# AMP.net
KiCad netlist of a schematic drawn in Altium Designer
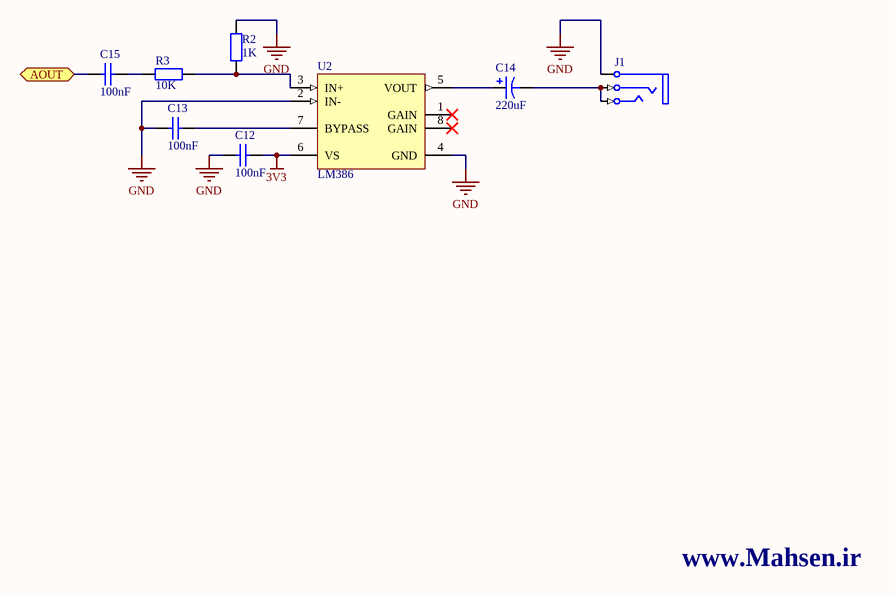
[diagram p0: AMP.SchDoc]

(export (version "E")
  (design (tool "Eeschema 10.0.6"))
  (components
    (comp (ref "C12")
      (value "100nF")
      (footprint "0805")
      (description "Capacitor")
      (fields (field (name "PUBLISHER") "Altium Limited"))
      (libsource (lib "Miscellaneous Devices") (part "Cap"))
    )
    (comp (ref "C13")
      (value "100nF")
      (footprint "0805")
      (description "Capacitor")
      (fields (field (name "PUBLISHER") "Altium Limited"))
      (libsource (lib "Miscellaneous Devices") (part "Cap"))
    )
    (comp (ref "C14")
      (value "220uF")
      (footprint "C0805")
      (description "Polarized Capacitor (Surface Mount)")
      (fields (field (name "PUBLISHER") "Altium Limited"))
      (libsource (lib "Miscellaneous Devices") (part "Cap Pol3"))
    )
    (comp (ref "C15")
      (value "100nF")
      (footprint "0805")
      (description "Capacitor")
      (fields (field (name "PUBLISHER") "Altium Limited"))
      (libsource (lib "Miscellaneous Devices") (part "Cap"))
    )
    (comp (ref "J1")
      (value "Phonejack3")
      (footprint "JACK/6-V3")
      (description "Jack Socket, 1/4\" [6.5mm], Thru-Hole, Vertical, 3-Conductor Open Circuit (Non-Normalling)")
      (fields (field (name "PUBLISHER") "Altium Limited"))
      (libsource (lib "Miscellaneous Connectors") (part "Phonejack3"))
    )
    (comp (ref "R2")
      (value "1K")
      (footprint "0805")
      (description "Resistor")
      (fields (field (name "PUBLISHER") "Altium Limited"))
      (libsource (lib "Miscellaneous Devices") (part "Res2"))
    )
    (comp (ref "R3")
      (value "10K")
      (footprint "0805")
      (description "Resistor")
      (fields (field (name "PUBLISHER") "Altium Limited"))
      (libsource (lib "") (part "Res2_1"))
    )
    (comp (ref "U2")
      (value "LM386")
      (footprint "M08A_L")
      (description "Low Voltage Audio Power Amplifier, 8-pin Narrow SOIC")
      (fields
        (field (name "PARTNUMBER") "LM386MX-1")
        (field (name "MANUFACTURER") "National Semiconductor")
        (field (name "PUBLISHER") "Altium Limited")
      )
      (libsource (lib "NSC Audio") (part "LM386MX-1"))
    )
  )
  (nets
    (net (code "1") (name "/AOUT") (class "Default")
      (node (ref "C15") (pin "2") (pinfunction "2_2") (pintype "passive"))
    )
    (net (code "2") (name "3V3") (class "Default")
      (node (ref "C12") (pin "1") (pinfunction "1_1") (pintype "passive"))
      (node (ref "U2") (pin "6") (pinfunction "VS_6") (pintype "power_in"))
    )
    (net (code "3") (name "GND") (class "Default")
      (node (ref "C12") (pin "2") (pinfunction "2_2") (pintype "passive"))
      (node (ref "C13") (pin "2") (pinfunction "2_2") (pintype "passive"))
      (node (ref "J1") (pin "5") (pinfunction "S_5") (pintype "power_in"))
      (node (ref "R2") (pin "2") (pinfunction "2_2") (pintype "passive"))
      (node (ref "U2") (pin "2") (pinfunction "IN-_2") (pintype "input"))
      (node (ref "U2") (pin "4") (pinfunction "GND_4") (pintype "power_in"))
    )
    (net (code "4") (name "Net-(C15-Pad1)") (class "Default")
      (node (ref "C15") (pin "1") (pinfunction "1_1") (pintype "passive"))
      (node (ref "R3") (pin "1") (pinfunction "1_1") (pintype "passive"))
    )
    (net (code "5") (name "Net-(J1-R)") (class "Default")
      (node (ref "C14") (pin "2") (pinfunction "2_2") (pintype "passive"))
      (node (ref "J1") (pin "1") (pinfunction "T_1") (pintype "input"))
      (node (ref "J1") (pin "3") (pinfunction "R_3") (pintype "input"))
    )
    (net (code "6") (name "Net-(U2-BYPASS)") (class "Default")
      (node (ref "C13") (pin "1") (pinfunction "1_1") (pintype "passive"))
      (node (ref "U2") (pin "7") (pinfunction "BYPASS_7") (pintype "passive"))
    )
    (net (code "7") (name "Net-(U2-IN+)") (class "Default")
      (node (ref "R2") (pin "1") (pinfunction "1_1") (pintype "passive"))
      (node (ref "R3") (pin "2") (pinfunction "2_2") (pintype "passive"))
      (node (ref "U2") (pin "3") (pinfunction "IN+_3") (pintype "input"))
    )
    (net (code "8") (name "Net-(U2-VOUT)") (class "Default")
      (node (ref "C14") (pin "1") (pinfunction "1_1") (pintype "passive"))
      (node (ref "U2") (pin "5") (pinfunction "VOUT_5") (pintype "output"))
    )
    (net (code "9") (name "unconnected-(U2-GAIN-Pad1)") (class "Default")
      (node (ref "U2") (pin "1") (pinfunction "GAIN_1") (pintype "passive+no_connect"))
    )
    (net (code "10") (name "unconnected-(U2-GAIN-Pad8)") (class "Default")
      (node (ref "U2") (pin "8") (pinfunction "GAIN_8") (pintype "passive+no_connect"))
    )
  )
)
